# I2C_Module_v8_wo_PS.net
KiCad netlist of a schematic drawn in EAGLE
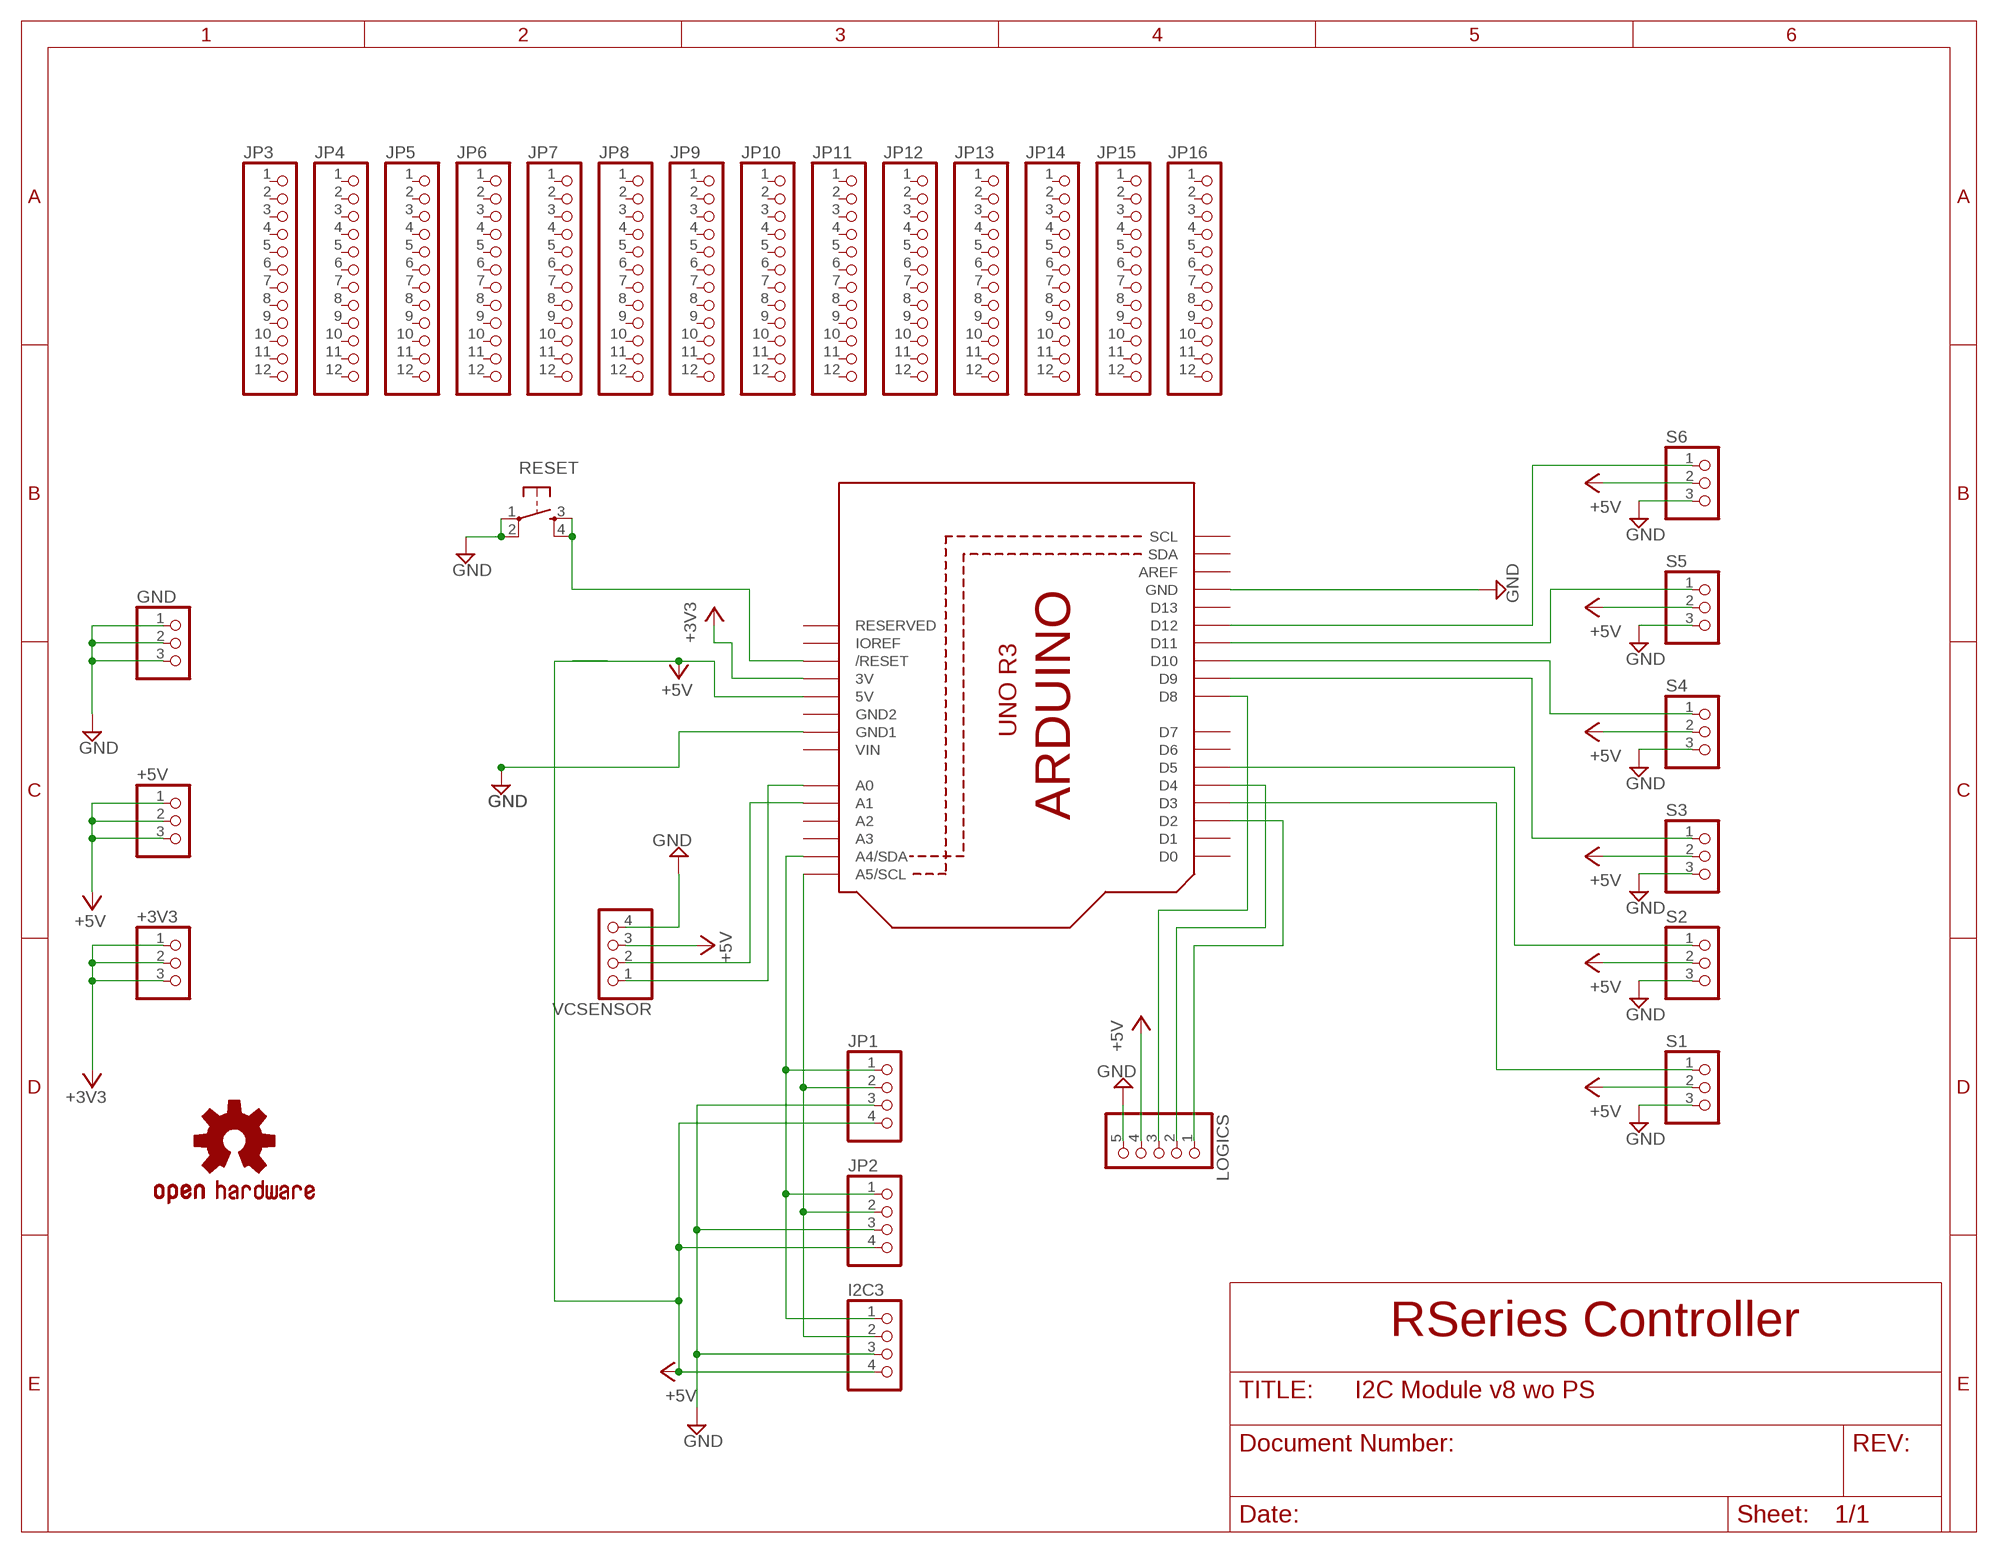
[diagram p0: schematic, sheet 1]

(export (version "E")
  (design (tool "Eeschema 10.0.6"))
  (components
    (comp (ref "+3V3")
      (value "PINHD-1X3CB")
      (footprint "eagle-import:1X03-CLEANBIG")
      (libsource (lib "eagle-import") (part "PINHD-1X3CB"))
    )
    (comp (ref "+5V")
      (value "PINHD-1X3CB")
      (footprint "eagle-import:1X03-CLEANBIG")
      (libsource (lib "eagle-import") (part "PINHD-1X3CB"))
    )
    (comp (ref "GND")
      (value "PINHD-1X3CB")
      (footprint "eagle-import:1X03-CLEANBIG")
      (libsource (lib "eagle-import") (part "PINHD-1X3CB"))
    )
    (comp (ref "I2C3")
      (value "PINHD-1X4")
      (footprint "eagle-import:1X04")
      (libsource (lib "eagle-import") (part "PINHD-1X4"))
    )
    (comp (ref "JP1")
      (value "PINHD-1X4")
      (footprint "eagle-import:1X04")
      (libsource (lib "eagle-import") (part "PINHD-1X4"))
    )
    (comp (ref "JP2")
      (value "PINHD-1X4")
      (footprint "eagle-import:1X04")
      (libsource (lib "eagle-import") (part "PINHD-1X4"))
    )
    (comp (ref "JP3")
      (value "PINHD-1X12-CB")
      (footprint "eagle-import:1X12-CB")
      (libsource (lib "eagle-import") (part "PINHD-1X12-CB"))
    )
    (comp (ref "JP4")
      (value "PINHD-1X12-CB")
      (footprint "eagle-import:1X12-CB")
      (libsource (lib "eagle-import") (part "PINHD-1X12-CB"))
    )
    (comp (ref "JP5")
      (value "PINHD-1X12-CB")
      (footprint "eagle-import:1X12-CB")
      (libsource (lib "eagle-import") (part "PINHD-1X12-CB"))
    )
    (comp (ref "JP6")
      (value "PINHD-1X12-CB")
      (footprint "eagle-import:1X12-CB")
      (libsource (lib "eagle-import") (part "PINHD-1X12-CB"))
    )
    (comp (ref "JP7")
      (value "PINHD-1X12-CB")
      (footprint "eagle-import:1X12-CB")
      (libsource (lib "eagle-import") (part "PINHD-1X12-CB"))
    )
    (comp (ref "JP8")
      (value "PINHD-1X12-CB")
      (footprint "eagle-import:1X12-CB")
      (libsource (lib "eagle-import") (part "PINHD-1X12-CB"))
    )
    (comp (ref "JP9")
      (value "PINHD-1X12-CB")
      (footprint "eagle-import:1X12-CB")
      (libsource (lib "eagle-import") (part "PINHD-1X12-CB"))
    )
    (comp (ref "JP10")
      (value "PINHD-1X12-CB")
      (footprint "eagle-import:1X12-CB")
      (libsource (lib "eagle-import") (part "PINHD-1X12-CB"))
    )
    (comp (ref "JP11")
      (value "PINHD-1X12-CB")
      (footprint "eagle-import:1X12-CB")
      (libsource (lib "eagle-import") (part "PINHD-1X12-CB"))
    )
    (comp (ref "JP12")
      (value "PINHD-1X12-CB")
      (footprint "eagle-import:1X12-CB")
      (libsource (lib "eagle-import") (part "PINHD-1X12-CB"))
    )
    (comp (ref "JP13")
      (value "PINHD-1X12-CB")
      (footprint "eagle-import:1X12-CB")
      (libsource (lib "eagle-import") (part "PINHD-1X12-CB"))
    )
    (comp (ref "JP14")
      (value "PINHD-1X12-CB")
      (footprint "eagle-import:1X12-CB")
      (libsource (lib "eagle-import") (part "PINHD-1X12-CB"))
    )
    (comp (ref "JP15")
      (value "PINHD-1X12-CB")
      (footprint "eagle-import:1X12-CB")
      (libsource (lib "eagle-import") (part "PINHD-1X12-CB"))
    )
    (comp (ref "JP16")
      (value "PINHD-1X12-CB")
      (footprint "eagle-import:1X12-CB")
      (libsource (lib "eagle-import") (part "PINHD-1X12-CB"))
    )
    (comp (ref "LOGICS")
      (value "PINHD-1X5")
      (footprint "eagle-import:1X05")
      (libsource (lib "eagle-import") (part "PINHD-1X5"))
    )
    (comp (ref "RESET")
      (value "TAC_SWITCHPTH")
      (footprint "eagle-import:TACTILE-PTH")
      (libsource (lib "eagle-import") (part "TAC_SWITCHPTH"))
    )
    (comp (ref "S1")
      (value "PINHD-1X3")
      (footprint "eagle-import:1X03")
      (libsource (lib "eagle-import") (part "PINHD-1X3"))
    )
    (comp (ref "S2")
      (value "PINHD-1X3")
      (footprint "eagle-import:1X03")
      (libsource (lib "eagle-import") (part "PINHD-1X3"))
    )
    (comp (ref "S3")
      (value "PINHD-1X3")
      (footprint "eagle-import:1X03")
      (libsource (lib "eagle-import") (part "PINHD-1X3"))
    )
    (comp (ref "S4")
      (value "PINHD-1X3")
      (footprint "eagle-import:1X03")
      (libsource (lib "eagle-import") (part "PINHD-1X3"))
    )
    (comp (ref "S5")
      (value "PINHD-1X3")
      (footprint "eagle-import:1X03")
      (libsource (lib "eagle-import") (part "PINHD-1X3"))
    )
    (comp (ref "S6")
      (value "PINHD-1X3")
      (footprint "eagle-import:1X03")
      (libsource (lib "eagle-import") (part "PINHD-1X3"))
    )
    (comp (ref "U$1")
      (value "OSHW-LOGOM")
      (footprint "eagle-import:OSHW-LOGO-M")
      (libsource (lib "eagle-import") (part "OSHW-LOGOM"))
    )
    (comp (ref "U1")
      (value "ARDUINOR3-DIMENSION")
      (footprint "eagle-import:ARDUINOR3")
      (libsource (lib "eagle-import") (part "ARDUINOR3-DIMENSION"))
    )
    (comp (ref "VCSENSOR")
      (value "PINHD-1X4")
      (footprint "eagle-import:1X04")
      (libsource (lib "eagle-import") (part "PINHD-1X4"))
    )
  )
  (nets
    (net (code "1") (name "+3V3") (class "Default")
      (node (ref "+3V3") (pin "1") (pinfunction "1_1") (pintype "passive"))
      (node (ref "+3V3") (pin "2") (pinfunction "2_2") (pintype "passive"))
      (node (ref "+3V3") (pin "3") (pinfunction "3_3") (pintype "passive"))
      (node (ref "U1") (pin "3V") (pinfunction "3V_3V") (pintype "power_in"))
    )
    (net (code "2") (name "+5V") (class "Default")
      (node (ref "+5V") (pin "1") (pinfunction "1_1") (pintype "passive"))
      (node (ref "+5V") (pin "2") (pinfunction "2_2") (pintype "passive"))
      (node (ref "+5V") (pin "3") (pinfunction "3_3") (pintype "passive"))
      (node (ref "I2C3") (pin "4") (pinfunction "4_4") (pintype "passive"))
      (node (ref "JP1") (pin "4") (pinfunction "4_4") (pintype "passive"))
      (node (ref "JP2") (pin "4") (pinfunction "4_4") (pintype "passive"))
      (node (ref "LOGICS") (pin "4") (pinfunction "4_4") (pintype "passive"))
      (node (ref "S1") (pin "2") (pinfunction "2_2") (pintype "passive"))
      (node (ref "S2") (pin "2") (pinfunction "2_2") (pintype "passive"))
      (node (ref "S3") (pin "2") (pinfunction "2_2") (pintype "passive"))
      (node (ref "S4") (pin "2") (pinfunction "2_2") (pintype "passive"))
      (node (ref "S5") (pin "2") (pinfunction "2_2") (pintype "passive"))
      (node (ref "S6") (pin "2") (pinfunction "2_2") (pintype "passive"))
      (node (ref "U1") (pin "5V") (pinfunction "5V_5V") (pintype "power_in"))
      (node (ref "VCSENSOR") (pin "3") (pinfunction "3_3") (pintype "passive"))
    )
    (net (code "3") (name "/GND2") (class "Default")
      (node (ref "U1") (pin "GND2") (pinfunction "GND2_GND2") (pintype "power_in"))
    )
    (net (code "4") (name "/VIN") (class "Default")
      (node (ref "U1") (pin "VIN") (pinfunction "VIN_VIN") (pintype "power_in"))
    )
    (net (code "5") (name "GND") (class "Default")
      (node (ref "GND") (pin "1") (pinfunction "1_1") (pintype "passive"))
      (node (ref "GND") (pin "2") (pinfunction "2_2") (pintype "passive"))
      (node (ref "GND") (pin "3") (pinfunction "3_3") (pintype "passive"))
      (node (ref "I2C3") (pin "3") (pinfunction "3_3") (pintype "passive"))
      (node (ref "JP1") (pin "3") (pinfunction "3_3") (pintype "passive"))
      (node (ref "JP2") (pin "3") (pinfunction "3_3") (pintype "passive"))
      (node (ref "LOGICS") (pin "5") (pinfunction "5_5") (pintype "passive"))
      (node (ref "RESET") (pin "1") (pinfunction "1_1") (pintype "passive"))
      (node (ref "RESET") (pin "2") (pinfunction "2_2") (pintype "passive"))
      (node (ref "S1") (pin "3") (pinfunction "3_3") (pintype "passive"))
      (node (ref "S2") (pin "3") (pinfunction "3_3") (pintype "passive"))
      (node (ref "S3") (pin "3") (pinfunction "3_3") (pintype "passive"))
      (node (ref "S4") (pin "3") (pinfunction "3_3") (pintype "passive"))
      (node (ref "S5") (pin "3") (pinfunction "3_3") (pintype "passive"))
      (node (ref "S6") (pin "3") (pinfunction "3_3") (pintype "passive"))
      (node (ref "U1") (pin "GND") (pinfunction "GND_GND") (pintype "power_in"))
      (node (ref "U1") (pin "GND1") (pinfunction "GND1_GND1") (pintype "power_in"))
      (node (ref "VCSENSOR") (pin "4") (pinfunction "4_4") (pintype "passive"))
    )
    (net (code "6") (name "Net-(LOGICS-Pad1)") (class "Default")
      (node (ref "LOGICS") (pin "1") (pinfunction "1_1") (pintype "passive"))
      (node (ref "U1") (pin "D2") (pinfunction "D2_D2") (pintype "bidirectional"))
    )
    (net (code "7") (name "Net-(LOGICS-Pad2)") (class "Default")
      (node (ref "LOGICS") (pin "2") (pinfunction "2_2") (pintype "passive"))
      (node (ref "U1") (pin "D4") (pinfunction "D4_D4") (pintype "bidirectional"))
    )
    (net (code "8") (name "Net-(LOGICS-Pad3)") (class "Default")
      (node (ref "LOGICS") (pin "3") (pinfunction "3_3") (pintype "passive"))
      (node (ref "U1") (pin "D8") (pinfunction "D8_D8") (pintype "bidirectional"))
    )
    (net (code "9") (name "Net-(S1-Pad1)") (class "Default")
      (node (ref "S1") (pin "1") (pinfunction "1_1") (pintype "passive"))
      (node (ref "U1") (pin "D3") (pinfunction "D3_D3") (pintype "bidirectional"))
    )
    (net (code "10") (name "Net-(S2-Pad1)") (class "Default")
      (node (ref "S2") (pin "1") (pinfunction "1_1") (pintype "passive"))
      (node (ref "U1") (pin "D5") (pinfunction "D5_D5") (pintype "bidirectional"))
    )
    (net (code "11") (name "Net-(S3-Pad1)") (class "Default")
      (node (ref "S3") (pin "1") (pinfunction "1_1") (pintype "passive"))
      (node (ref "U1") (pin "D9") (pinfunction "D9_D9") (pintype "bidirectional"))
    )
    (net (code "12") (name "Net-(S4-Pad1)") (class "Default")
      (node (ref "S4") (pin "1") (pinfunction "1_1") (pintype "passive"))
      (node (ref "U1") (pin "D10") (pinfunction "D10_D10") (pintype "bidirectional"))
    )
    (net (code "13") (name "Net-(S5-Pad1)") (class "Default")
      (node (ref "S5") (pin "1") (pinfunction "1_1") (pintype "passive"))
      (node (ref "U1") (pin "D11") (pinfunction "D11_D11") (pintype "bidirectional"))
    )
    (net (code "14") (name "Net-(S6-Pad1)") (class "Default")
      (node (ref "S6") (pin "1") (pinfunction "1_1") (pintype "passive"))
      (node (ref "U1") (pin "D12") (pinfunction "D12_D12") (pintype "bidirectional"))
    )
    (net (code "15") (name "Net-(U1-A4{slash}SDA)") (class "Default")
      (node (ref "I2C3") (pin "1") (pinfunction "1_1") (pintype "passive"))
      (node (ref "JP1") (pin "1") (pinfunction "1_1") (pintype "passive"))
      (node (ref "JP2") (pin "1") (pinfunction "1_1") (pintype "passive"))
      (node (ref "U1") (pin "A4") (pinfunction "A4/SDA_A4") (pintype "bidirectional"))
    )
    (net (code "16") (name "Net-(U1-A5{slash}SCL)") (class "Default")
      (node (ref "I2C3") (pin "2") (pinfunction "2_2") (pintype "passive"))
      (node (ref "JP1") (pin "2") (pinfunction "2_2") (pintype "passive"))
      (node (ref "JP2") (pin "2") (pinfunction "2_2") (pintype "passive"))
      (node (ref "U1") (pin "A5") (pinfunction "A5/SCL_A5") (pintype "bidirectional"))
    )
    (net (code "17") (name "Net-(U1-PadA0)") (class "Default")
      (node (ref "U1") (pin "A0") (pinfunction "A0_A0") (pintype "bidirectional"))
      (node (ref "VCSENSOR") (pin "1") (pinfunction "1_1") (pintype "passive"))
    )
    (net (code "18") (name "Net-(U1-PadA1)") (class "Default")
      (node (ref "U1") (pin "A1") (pinfunction "A1_A1") (pintype "bidirectional"))
      (node (ref "VCSENSOR") (pin "2") (pinfunction "2_2") (pintype "passive"))
    )
    (net (code "19") (name "Net-(U1-{slash}RESET)") (class "Default")
      (node (ref "RESET") (pin "3") (pinfunction "3_3") (pintype "passive"))
      (node (ref "RESET") (pin "4") (pinfunction "4_4") (pintype "passive"))
      (node (ref "U1") (pin "RESET") (pinfunction "/RESET_RESET") (pintype "bidirectional"))
    )
    (net (code "20") (name "unconnected-(JP3-Pad1)") (class "Default")
      (node (ref "JP3") (pin "1") (pinfunction "1_1") (pintype "passive"))
    )
    (net (code "21") (name "unconnected-(JP3-Pad2)") (class "Default")
      (node (ref "JP3") (pin "2") (pinfunction "2_2") (pintype "passive"))
    )
    (net (code "22") (name "unconnected-(JP3-Pad3)") (class "Default")
      (node (ref "JP3") (pin "3") (pinfunction "3_3") (pintype "passive"))
    )
    (net (code "23") (name "unconnected-(JP3-Pad4)") (class "Default")
      (node (ref "JP3") (pin "4") (pinfunction "4_4") (pintype "passive"))
    )
    (net (code "24") (name "unconnected-(JP3-Pad5)") (class "Default")
      (node (ref "JP3") (pin "5") (pinfunction "5_5") (pintype "passive"))
    )
    (net (code "25") (name "unconnected-(JP3-Pad6)") (class "Default")
      (node (ref "JP3") (pin "6") (pinfunction "6_6") (pintype "passive"))
    )
    (net (code "26") (name "unconnected-(JP3-Pad7)") (class "Default")
      (node (ref "JP3") (pin "7") (pinfunction "7_7") (pintype "passive"))
    )
    (net (code "27") (name "unconnected-(JP3-Pad8)") (class "Default")
      (node (ref "JP3") (pin "8") (pinfunction "8_8") (pintype "passive"))
    )
    (net (code "28") (name "unconnected-(JP3-Pad9)") (class "Default")
      (node (ref "JP3") (pin "9") (pinfunction "9_9") (pintype "passive"))
    )
    (net (code "29") (name "unconnected-(JP3-Pad10)") (class "Default")
      (node (ref "JP3") (pin "10") (pinfunction "10_10") (pintype "passive"))
    )
    (net (code "30") (name "unconnected-(JP3-Pad11)") (class "Default")
      (node (ref "JP3") (pin "11") (pinfunction "11_11") (pintype "passive"))
    )
    (net (code "31") (name "unconnected-(JP3-Pad12)") (class "Default")
      (node (ref "JP3") (pin "12") (pinfunction "12_12") (pintype "passive"))
    )
    (net (code "32") (name "unconnected-(JP4-Pad1)") (class "Default")
      (node (ref "JP4") (pin "1") (pinfunction "1_1") (pintype "passive"))
    )
    (net (code "33") (name "unconnected-(JP4-Pad2)") (class "Default")
      (node (ref "JP4") (pin "2") (pinfunction "2_2") (pintype "passive"))
    )
    (net (code "34") (name "unconnected-(JP4-Pad3)") (class "Default")
      (node (ref "JP4") (pin "3") (pinfunction "3_3") (pintype "passive"))
    )
    (net (code "35") (name "unconnected-(JP4-Pad4)") (class "Default")
      (node (ref "JP4") (pin "4") (pinfunction "4_4") (pintype "passive"))
    )
    (net (code "36") (name "unconnected-(JP4-Pad5)") (class "Default")
      (node (ref "JP4") (pin "5") (pinfunction "5_5") (pintype "passive"))
    )
    (net (code "37") (name "unconnected-(JP4-Pad6)") (class "Default")
      (node (ref "JP4") (pin "6") (pinfunction "6_6") (pintype "passive"))
    )
    (net (code "38") (name "unconnected-(JP4-Pad7)") (class "Default")
      (node (ref "JP4") (pin "7") (pinfunction "7_7") (pintype "passive"))
    )
    (net (code "39") (name "unconnected-(JP4-Pad8)") (class "Default")
      (node (ref "JP4") (pin "8") (pinfunction "8_8") (pintype "passive"))
    )
    (net (code "40") (name "unconnected-(JP4-Pad9)") (class "Default")
      (node (ref "JP4") (pin "9") (pinfunction "9_9") (pintype "passive"))
    )
    (net (code "41") (name "unconnected-(JP4-Pad10)") (class "Default")
      (node (ref "JP4") (pin "10") (pinfunction "10_10") (pintype "passive"))
    )
    (net (code "42") (name "unconnected-(JP4-Pad11)") (class "Default")
      (node (ref "JP4") (pin "11") (pinfunction "11_11") (pintype "passive"))
    )
    (net (code "43") (name "unconnected-(JP4-Pad12)") (class "Default")
      (node (ref "JP4") (pin "12") (pinfunction "12_12") (pintype "passive"))
    )
    (net (code "44") (name "unconnected-(JP5-Pad1)") (class "Default")
      (node (ref "JP5") (pin "1") (pinfunction "1_1") (pintype "passive"))
    )
    (net (code "45") (name "unconnected-(JP5-Pad2)") (class "Default")
      (node (ref "JP5") (pin "2") (pinfunction "2_2") (pintype "passive"))
    )
    (net (code "46") (name "unconnected-(JP5-Pad3)") (class "Default")
      (node (ref "JP5") (pin "3") (pinfunction "3_3") (pintype "passive"))
    )
    (net (code "47") (name "unconnected-(JP5-Pad4)") (class "Default")
      (node (ref "JP5") (pin "4") (pinfunction "4_4") (pintype "passive"))
    )
    (net (code "48") (name "unconnected-(JP5-Pad5)") (class "Default")
      (node (ref "JP5") (pin "5") (pinfunction "5_5") (pintype "passive"))
    )
    (net (code "49") (name "unconnected-(JP5-Pad6)") (class "Default")
      (node (ref "JP5") (pin "6") (pinfunction "6_6") (pintype "passive"))
    )
    (net (code "50") (name "unconnected-(JP5-Pad7)") (class "Default")
      (node (ref "JP5") (pin "7") (pinfunction "7_7") (pintype "passive"))
    )
    (net (code "51") (name "unconnected-(JP5-Pad8)") (class "Default")
      (node (ref "JP5") (pin "8") (pinfunction "8_8") (pintype "passive"))
    )
    (net (code "52") (name "unconnected-(JP5-Pad9)") (class "Default")
      (node (ref "JP5") (pin "9") (pinfunction "9_9") (pintype "passive"))
    )
    (net (code "53") (name "unconnected-(JP5-Pad10)") (class "Default")
      (node (ref "JP5") (pin "10") (pinfunction "10_10") (pintype "passive"))
    )
    (net (code "54") (name "unconnected-(JP5-Pad11)") (class "Default")
      (node (ref "JP5") (pin "11") (pinfunction "11_11") (pintype "passive"))
    )
    (net (code "55") (name "unconnected-(JP5-Pad12)") (class "Default")
      (node (ref "JP5") (pin "12") (pinfunction "12_12") (pintype "passive"))
    )
    (net (code "56") (name "unconnected-(JP6-Pad1)") (class "Default")
      (node (ref "JP6") (pin "1") (pinfunction "1_1") (pintype "passive"))
    )
    (net (code "57") (name "unconnected-(JP6-Pad2)") (class "Default")
      (node (ref "JP6") (pin "2") (pinfunction "2_2") (pintype "passive"))
    )
    (net (code "58") (name "unconnected-(JP6-Pad3)") (class "Default")
      (node (ref "JP6") (pin "3") (pinfunction "3_3") (pintype "passive"))
    )
    (net (code "59") (name "unconnected-(JP6-Pad4)") (class "Default")
      (node (ref "JP6") (pin "4") (pinfunction "4_4") (pintype "passive"))
    )
    (net (code "60") (name "unconnected-(JP6-Pad5)") (class "Default")
      (node (ref "JP6") (pin "5") (pinfunction "5_5") (pintype "passive"))
    )
    (net (code "61") (name "unconnected-(JP6-Pad6)") (class "Default")
      (node (ref "JP6") (pin "6") (pinfunction "6_6") (pintype "passive"))
    )
    (net (code "62") (name "unconnected-(JP6-Pad7)") (class "Default")
      (node (ref "JP6") (pin "7") (pinfunction "7_7") (pintype "passive"))
    )
    (net (code "63") (name "unconnected-(JP6-Pad8)") (class "Default")
      (node (ref "JP6") (pin "8") (pinfunction "8_8") (pintype "passive"))
    )
    (net (code "64") (name "unconnected-(JP6-Pad9)") (class "Default")
      (node (ref "JP6") (pin "9") (pinfunction "9_9") (pintype "passive"))
    )
    (net (code "65") (name "unconnected-(JP6-Pad10)") (class "Default")
      (node (ref "JP6") (pin "10") (pinfunction "10_10") (pintype "passive"))
    )
    (net (code "66") (name "unconnected-(JP6-Pad11)") (class "Default")
      (node (ref "JP6") (pin "11") (pinfunction "11_11") (pintype "passive"))
    )
    (net (code "67") (name "unconnected-(JP6-Pad12)") (class "Default")
      (node (ref "JP6") (pin "12") (pinfunction "12_12") (pintype "passive"))
    )
    (net (code "68") (name "unconnected-(JP7-Pad1)") (class "Default")
      (node (ref "JP7") (pin "1") (pinfunction "1_1") (pintype "passive"))
    )
    (net (code "69") (name "unconnected-(JP7-Pad2)") (class "Default")
      (node (ref "JP7") (pin "2") (pinfunction "2_2") (pintype "passive"))
    )
    (net (code "70") (name "unconnected-(JP7-Pad3)") (class "Default")
      (node (ref "JP7") (pin "3") (pinfunction "3_3") (pintype "passive"))
    )
    (net (code "71") (name "unconnected-(JP7-Pad4)") (class "Default")
      (node (ref "JP7") (pin "4") (pinfunction "4_4") (pintype "passive"))
    )
    (net (code "72") (name "unconnected-(JP7-Pad5)") (class "Default")
      (node (ref "JP7") (pin "5") (pinfunction "5_5") (pintype "passive"))
    )
    (net (code "73") (name "unconnected-(JP7-Pad6)") (class "Default")
      (node (ref "JP7") (pin "6") (pinfunction "6_6") (pintype "passive"))
    )
    (net (code "74") (name "unconnected-(JP7-Pad7)") (class "Default")
      (node (ref "JP7") (pin "7") (pinfunction "7_7") (pintype "passive"))
    )
    (net (code "75") (name "unconnected-(JP7-Pad8)") (class "Default")
      (node (ref "JP7") (pin "8") (pinfunction "8_8") (pintype "passive"))
    )
    (net (code "76") (name "unconnected-(JP7-Pad9)") (class "Default")
      (node (ref "JP7") (pin "9") (pinfunction "9_9") (pintype "passive"))
    )
    (net (code "77") (name "unconnected-(JP7-Pad10)") (class "Default")
      (node (ref "JP7") (pin "10") (pinfunction "10_10") (pintype "passive"))
    )
    (net (code "78") (name "unconnected-(JP7-Pad11)") (class "Default")
      (node (ref "JP7") (pin "11") (pinfunction "11_11") (pintype "passive"))
    )
    (net (code "79") (name "unconnected-(JP7-Pad12)") (class "Default")
      (node (ref "JP7") (pin "12") (pinfunction "12_12") (pintype "passive"))
    )
    (net (code "80") (name "unconnected-(JP8-Pad1)") (class "Default")
      (node (ref "JP8") (pin "1") (pinfunction "1_1") (pintype "passive"))
    )
    (net (code "81") (name "unconnected-(JP8-Pad2)") (class "Default")
      (node (ref "JP8") (pin "2") (pinfunction "2_2") (pintype "passive"))
    )
    (net (code "82") (name "unconnected-(JP8-Pad3)") (class "Default")
      (node (ref "JP8") (pin "3") (pinfunction "3_3") (pintype "passive"))
    )
    (net (code "83") (name "unconnected-(JP8-Pad4)") (class "Default")
      (node (ref "JP8") (pin "4") (pinfunction "4_4") (pintype "passive"))
    )
    (net (code "84") (name "unconnected-(JP8-Pad5)") (class "Default")
      (node (ref "JP8") (pin "5") (pinfunction "5_5") (pintype "passive"))
    )
    (net (code "85") (name "unconnected-(JP8-Pad6)") (class "Default")
      (node (ref "JP8") (pin "6") (pinfunction "6_6") (pintype "passive"))
    )
    (net (code "86") (name "unconnected-(JP8-Pad7)") (class "Default")
      (node (ref "JP8") (pin "7") (pinfunction "7_7") (pintype "passive"))
    )
    (net (code "87") (name "unconnected-(JP8-Pad8)") (class "Default")
      (node (ref "JP8") (pin "8") (pinfunction "8_8") (pintype "passive"))
    )
    (net (code "88") (name "unconnected-(JP8-Pad9)") (class "Default")
      (node (ref "JP8") (pin "9") (pinfunction "9_9") (pintype "passive"))
    )
    (net (code "89") (name "unconnected-(JP8-Pad10)") (class "Default")
      (node (ref "JP8") (pin "10") (pinfunction "10_10") (pintype "passive"))
    )
    (net (code "90") (name "unconnected-(JP8-Pad11)") (class "Default")
      (node (ref "JP8") (pin "11") (pinfunction "11_11") (pintype "passive"))
    )
    (net (code "91") (name "unconnected-(JP8-Pad12)") (class "Default")
      (node (ref "JP8") (pin "12") (pinfunction "12_12") (pintype "passive"))
    )
    (net (code "92") (name "unconnected-(JP9-Pad1)") (class "Default")
      (node (ref "JP9") (pin "1") (pinfunction "1_1") (pintype "passive"))
    )
    (net (code "93") (name "unconnected-(JP9-Pad2)") (class "Default")
      (node (ref "JP9") (pin "2") (pinfunction "2_2") (pintype "passive"))
    )
    (net (code "94") (name "unconnected-(JP9-Pad3)") (class "Default")
      (node (ref "JP9") (pin "3") (pinfunction "3_3") (pintype "passive"))
    )
    (net (code "95") (name "unconnected-(JP9-Pad4)") (class "Default")
      (node (ref "JP9") (pin "4") (pinfunction "4_4") (pintype "passive"))
    )
    (net (code "96") (name "unconnected-(JP9-Pad5)") (class "Default")
      (node (ref "JP9") (pin "5") (pinfunction "5_5") (pintype "passive"))
    )
    (net (code "97") (name "unconnected-(JP9-Pad6)") (class "Default")
      (node (ref "JP9") (pin "6") (pinfunction "6_6") (pintype "passive"))
    )
    (net (code "98") (name "unconnected-(JP9-Pad7)") (class "Default")
      (node (ref "JP9") (pin "7") (pinfunction "7_7") (pintype "passive"))
    )
    (net (code "99") (name "unconnected-(JP9-Pad8)") (class "Default")
      (node (ref "JP9") (pin "8") (pinfunction "8_8") (pintype "passive"))
    )
    (net (code "100") (name "unconnected-(JP9-Pad9)") (class "Default")
      (node (ref "JP9") (pin "9") (pinfunction "9_9") (pintype "passive"))
    )
    (net (code "101") (name "unconnected-(JP9-Pad10)") (class "Default")
      (node (ref "JP9") (pin "10") (pinfunction "10_10") (pintype "passive"))
    )
    (net (code "102") (name "unconnected-(JP9-Pad11)") (class "Default")
      (node (ref "JP9") (pin "11") (pinfunction "11_11") (pintype "passive"))
    )
    (net (code "103") (name "unconnected-(JP9-Pad12)") (class "Default")
      (node (ref "JP9") (pin "12") (pinfunction "12_12") (pintype "passive"))
    )
    (net (code "104") (name "unconnected-(JP10-Pad1)") (class "Default")
      (node (ref "JP10") (pin "1") (pinfunction "1_1") (pintype "passive"))
    )
    (net (code "105") (name "unconnected-(JP10-Pad2)") (class "Default")
      (node (ref "JP10") (pin "2") (pinfunction "2_2") (pintype "passive"))
    )
    (net (code "106") (name "unconnected-(JP10-Pad3)") (class "Default")
      (node (ref "JP10") (pin "3") (pinfunction "3_3") (pintype "passive"))
    )
    (net (code "107") (name "unconnected-(JP10-Pad4)") (class "Default")
      (node (ref "JP10") (pin "4") (pinfunction "4_4") (pintype "passive"))
    )
    (net (code "108") (name "unconnected-(JP10-Pad5)") (class "Default")
      (node (ref "JP10") (pin "5") (pinfunction "5_5") (pintype "passive"))
    )
    (net (code "109") (name "unconnected-(JP10-Pad6)") (class "Default")
      (node (ref "JP10") (pin "6") (pinfunction "6_6") (pintype "passive"))
    )
    (net (code "110") (name "unconnected-(JP10-Pad7)") (class "Default")
      (node (ref "JP10") (pin "7") (pinfunction "7_7") (pintype "passive"))
    )
    (net (code "111") (name "unconnected-(JP10-Pad8)") (class "Default")
      (node (ref "JP10") (pin "8") (pinfunction "8_8") (pintype "passive"))
    )
    (net (code "112") (name "unconnected-(JP10-Pad9)") (class "Default")
      (node (ref "JP10") (pin "9") (pinfunction "9_9") (pintype "passive"))
    )
    (net (code "113") (name "unconnected-(JP10-Pad10)") (class "Default")
      (node (ref "JP10") (pin "10") (pinfunction "10_10") (pintype "passive"))
    )
    (net (code "114") (name "unconnected-(JP10-Pad11)") (class "Default")
      (node (ref "JP10") (pin "11") (pinfunction "11_11") (pintype "passive"))
    )
    (net (code "115") (name "unconnected-(JP10-Pad12)") (class "Default")
      (node (ref "JP10") (pin "12") (pinfunction "12_12") (pintype "passive"))
    )
    (net (code "116") (name "unconnected-(JP11-Pad1)") (class "Default")
      (node (ref "JP11") (pin "1") (pinfunction "1_1") (pintype "passive"))
    )
    (net (code "117") (name "unconnected-(JP11-Pad2)") (class "Default")
      (node (ref "JP11") (pin "2") (pinfunction "2_2") (pintype "passive"))
    )
    (net (code "118") (name "unconnected-(JP11-Pad3)") (class "Default")
      (node (ref "JP11") (pin "3") (pinfunction "3_3") (pintype "passive"))
    )
    (net (code "119") (name "unconnected-(JP11-Pad4)") (class "Default")
      (node (ref "JP11") (pin "4") (pinfunction "4_4") (pintype "passive"))
    )
    (net (code "120") (name "unconnected-(JP11-Pad5)") (class "Default")
      (node (ref "JP11") (pin "5") (pinfunction "5_5") (pintype "passive"))
    )
    (net (code "121") (name "unconnected-(JP11-Pad6)") (class "Default")
      (node (ref "JP11") (pin "6") (pinfunction "6_6") (pintype "passive"))
    )
    (net (code "122") (name "unconnected-(JP11-Pad7)") (class "Default")
      (node (ref "JP11") (pin "7") (pinfunction "7_7") (pintype "passive"))
    )
    (net (code "123") (name "unconnected-(JP11-Pad8)") (class "Default")
      (node (ref "JP11") (pin "8") (pinfunction "8_8") (pintype "passive"))
    )
    (net (code "124") (name "unconnected-(JP11-Pad9)") (class "Default")
      (node (ref "JP11") (pin "9") (pinfunction "9_9") (pintype "passive"))
    )
    (net (code "125") (name "unconnected-(JP11-Pad10)") (class "Default")
      (node (ref "JP11") (pin "10") (pinfunction "10_10") (pintype "passive"))
    )
    (net (code "126") (name "unconnected-(JP11-Pad11)") (class "Default")
      (node (ref "JP11") (pin "11") (pinfunction "11_11") (pintype "passive"))
    )
    (net (code "127") (name "unconnected-(JP11-Pad12)") (class "Default")
      (node (ref "JP11") (pin "12") (pinfunction "12_12") (pintype "passive"))
    )
    (net (code "128") (name "unconnected-(JP12-Pad1)") (class "Default")
      (node (ref "JP12") (pin "1") (pinfunction "1_1") (pintype "passive"))
    )
    (net (code "129") (name "unconnected-(JP12-Pad2)") (class "Default")
      (node (ref "JP12") (pin "2") (pinfunction "2_2") (pintype "passive"))
    )
    (net (code "130") (name "unconnected-(JP12-Pad3)") (class "Default")
      (node (ref "JP12") (pin "3") (pinfunction "3_3") (pintype "passive"))
    )
    (net (code "131") (name "unconnected-(JP12-Pad4)") (class "Default")
      (node (ref "JP12") (pin "4") (pinfunction "4_4") (pintype "passive"))
    )
    (net (code "132") (name "unconnected-(JP12-Pad5)") (class "Default")
      (node (ref "JP12") (pin "5") (pinfunction "5_5") (pintype "passive"))
    )
    (net (code "133") (name "unconnected-(JP12-Pad6)") (class "Default")
      (node (ref "JP12") (pin "6") (pinfunction "6_6") (pintype "passive"))
    )
    (net (code "134") (name "unconnected-(JP12-Pad7)") (class "Default")
      (node (ref "JP12") (pin "7") (pinfunction "7_7") (pintype "passive"))
    )
    (net (code "135") (name "unconnected-(JP12-Pad8)") (class "Default")
      (node (ref "JP12") (pin "8") (pinfunction "8_8") (pintype "passive"))
    )
    (net (code "136") (name "unconnected-(JP12-Pad9)") (class "Default")
      (node (ref "JP12") (pin "9") (pinfunction "9_9") (pintype "passive"))
    )
    (net (code "137") (name "unconnected-(JP12-Pad10)") (class "Default")
      (node (ref "JP12") (pin "10") (pinfunction "10_10") (pintype "passive"))
    )
    (net (code "138") (name "unconnected-(JP12-Pad11)") (class "Default")
      (node (ref "JP12") (pin "11") (pinfunction "11_11") (pintype "passive"))
    )
    (net (code "139") (name "unconnected-(JP12-Pad12)") (class "Default")
      (node (ref "JP12") (pin "12") (pinfunction "12_12") (pintype "passive"))
    )
    (net (code "140") (name "unconnected-(JP13-Pad1)") (class "Default")
      (node (ref "JP13") (pin "1") (pinfunction "1_1") (pintype "passive"))
    )
    (net (code "141") (name "unconnected-(JP13-Pad2)") (class "Default")
      (node (ref "JP13") (pin "2") (pinfunction "2_2") (pintype "passive"))
    )
    (net (code "142") (name "unconnected-(JP13-Pad3)") (class "Default")
      (node (ref "JP13") (pin "3") (pinfunction "3_3") (pintype "passive"))
    )
    (net (code "143") (name "unconnected-(JP13-Pad4)") (class "Default")
      (node (ref "JP13") (pin "4") (pinfunction "4_4") (pintype "passive"))
    )
    (net (code "144") (name "unconnected-(JP13-Pad5)") (class "Default")
      (node (ref "JP13") (pin "5") (pinfunction "5_5") (pintype "passive"))
    )
    (net (code "145") (name "unconnected-(JP13-Pad6)") (class "Default")
      (node (ref "JP13") (pin "6") (pinfunction "6_6") (pintype "passive"))
    )
    (net (code "146") (name "unconnected-(JP13-Pad7)") (class "Default")
      (node (ref "JP13") (pin "7") (pinfunction "7_7") (pintype "passive"))
    )
    (net (code "147") (name "unconnected-(JP13-Pad8)") (class "Default")
      (node (ref "JP13") (pin "8") (pinfunction "8_8") (pintype "passive"))
    )
    (net (code "148") (name "unconnected-(JP13-Pad9)") (class "Default")
      (node (ref "JP13") (pin "9") (pinfunction "9_9") (pintype "passive"))
    )
    (net (code "149") (name "unconnected-(JP13-Pad10)") (class "Default")
      (node (ref "JP13") (pin "10") (pinfunction "10_10") (pintype "passive"))
    )
    (net (code "150") (name "unconnected-(JP13-Pad11)") (class "Default")
      (node (ref "JP13") (pin "11") (pinfunction "11_11") (pintype "passive"))
    )
    (net (code "151") (name "unconnected-(JP13-Pad12)") (class "Default")
      (node (ref "JP13") (pin "12") (pinfunction "12_12") (pintype "passive"))
    )
    (net (code "152") (name "unconnected-(JP14-Pad1)") (class "Default")
      (node (ref "JP14") (pin "1") (pinfunction "1_1") (pintype "passive"))
    )
    (net (code "153") (name "unconnected-(JP14-Pad2)") (class "Default")
      (node (ref "JP14") (pin "2") (pinfunction "2_2") (pintype "passive"))
    )
    (net (code "154") (name "unconnected-(JP14-Pad3)") (class "Default")
      (node (ref "JP14") (pin "3") (pinfunction "3_3") (pintype "passive"))
    )
    (net (code "155") (name "unconnected-(JP14-Pad4)") (class "Default")
      (node (ref "JP14") (pin "4") (pinfunction "4_4") (pintype "passive"))
    )
    (net (code "156") (name "unconnected-(JP14-Pad5)") (class "Default")
      (node (ref "JP14") (pin "5") (pinfunction "5_5") (pintype "passive"))
    )
    (net (code "157") (name "unconnected-(JP14-Pad6)") (class "Default")
      (node (ref "JP14") (pin "6") (pinfunction "6_6") (pintype "passive"))
    )
    (net (code "158") (name "unconnected-(JP14-Pad7)") (class "Default")
      (node (ref "JP14") (pin "7") (pinfunction "7_7") (pintype "passive"))
    )
    (net (code "159") (name "unconnected-(JP14-Pad8)") (class "Default")
      (node (ref "JP14") (pin "8") (pinfunction "8_8") (pintype "passive"))
    )
    (net (code "160") (name "unconnected-(JP14-Pad9)") (class "Default")
      (node (ref "JP14") (pin "9") (pinfunction "9_9") (pintype "passive"))
    )
    (net (code "161") (name "unconnected-(JP14-Pad10)") (class "Default")
      (node (ref "JP14") (pin "10") (pinfunction "10_10") (pintype "passive"))
    )
    (net (code "162") (name "unconnected-(JP14-Pad11)") (class "Default")
      (node (ref "JP14") (pin "11") (pinfunction "11_11") (pintype "passive"))
    )
    (net (code "163") (name "unconnected-(JP14-Pad12)") (class "Default")
      (node (ref "JP14") (pin "12") (pinfunction "12_12") (pintype "passive"))
    )
    (net (code "164") (name "unconnected-(JP15-Pad1)") (class "Default")
      (node (ref "JP15") (pin "1") (pinfunction "1_1") (pintype "passive"))
    )
    (net (code "165") (name "unconnected-(JP15-Pad2)") (class "Default")
      (node (ref "JP15") (pin "2") (pinfunction "2_2") (pintype "passive"))
    )
    (net (code "166") (name "unconnected-(JP15-Pad3)") (class "Default")
      (node (ref "JP15") (pin "3") (pinfunction "3_3") (pintype "passive"))
    )
    (net (code "167") (name "unconnected-(JP15-Pad4)") (class "Default")
      (node (ref "JP15") (pin "4") (pinfunction "4_4") (pintype "passive"))
    )
    (net (code "168") (name "unconnected-(JP15-Pad5)") (class "Default")
      (node (ref "JP15") (pin "5") (pinfunction "5_5") (pintype "passive"))
    )
    (net (code "169") (name "unconnected-(JP15-Pad6)") (class "Default")
      (node (ref "JP15") (pin "6") (pinfunction "6_6") (pintype "passive"))
    )
    (net (code "170") (name "unconnected-(JP15-Pad7)") (class "Default")
      (node (ref "JP15") (pin "7") (pinfunction "7_7") (pintype "passive"))
    )
    (net (code "171") (name "unconnected-(JP15-Pad8)") (class "Default")
      (node (ref "JP15") (pin "8") (pinfunction "8_8") (pintype "passive"))
    )
    (net (code "172") (name "unconnected-(JP15-Pad9)") (class "Default")
      (node (ref "JP15") (pin "9") (pinfunction "9_9") (pintype "passive"))
    )
    (net (code "173") (name "unconnected-(JP15-Pad10)") (class "Default")
      (node (ref "JP15") (pin "10") (pinfunction "10_10") (pintype "passive"))
    )
    (net (code "174") (name "unconnected-(JP15-Pad11)") (class "Default")
      (node (ref "JP15") (pin "11") (pinfunction "11_11") (pintype "passive"))
    )
    (net (code "175") (name "unconnected-(JP15-Pad12)") (class "Default")
      (node (ref "JP15") (pin "12") (pinfunction "12_12") (pintype "passive"))
    )
    (net (code "176") (name "unconnected-(JP16-Pad1)") (class "Default")
      (node (ref "JP16") (pin "1") (pinfunction "1_1") (pintype "passive"))
    )
    (net (code "177") (name "unconnected-(JP16-Pad2)") (class "Default")
      (node (ref "JP16") (pin "2") (pinfunction "2_2") (pintype "passive"))
    )
    (net (code "178") (name "unconnected-(JP16-Pad3)") (class "Default")
      (node (ref "JP16") (pin "3") (pinfunction "3_3") (pintype "passive"))
    )
    (net (code "179") (name "unconnected-(JP16-Pad4)") (class "Default")
      (node (ref "JP16") (pin "4") (pinfunction "4_4") (pintype "passive"))
    )
    (net (code "180") (name "unconnected-(JP16-Pad5)") (class "Default")
      (node (ref "JP16") (pin "5") (pinfunction "5_5") (pintype "passive"))
    )
    (net (code "181") (name "unconnected-(JP16-Pad6)") (class "Default")
      (node (ref "JP16") (pin "6") (pinfunction "6_6") (pintype "passive"))
    )
    (net (code "182") (name "unconnected-(JP16-Pad7)") (class "Default")
      (node (ref "JP16") (pin "7") (pinfunction "7_7") (pintype "passive"))
    )
    (net (code "183") (name "unconnected-(JP16-Pad8)") (class "Default")
      (node (ref "JP16") (pin "8") (pinfunction "8_8") (pintype "passive"))
    )
    (net (code "184") (name "unconnected-(JP16-Pad9)") (class "Default")
      (node (ref "JP16") (pin "9") (pinfunction "9_9") (pintype "passive"))
    )
    (net (code "185") (name "unconnected-(JP16-Pad10)") (class "Default")
      (node (ref "JP16") (pin "10") (pinfunction "10_10") (pintype "passive"))
    )
    (net (code "186") (name "unconnected-(JP16-Pad11)") (class "Default")
      (node (ref "JP16") (pin "11") (pinfunction "11_11") (pintype "passive"))
    )
    (net (code "187") (name "unconnected-(JP16-Pad12)") (class "Default")
      (node (ref "JP16") (pin "12") (pinfunction "12_12") (pintype "passive"))
    )
    (net (code "188") (name "unconnected-(U1-PadA2)") (class "Default")
      (node (ref "U1") (pin "A2") (pinfunction "A2_A2") (pintype "bidirectional"))
    )
    (net (code "189") (name "unconnected-(U1-PadA3)") (class "Default")
      (node (ref "U1") (pin "A3") (pinfunction "A3_A3") (pintype "bidirectional"))
    )
    (net (code "190") (name "unconnected-(U1-PadAREF)") (class "Default")
      (node (ref "U1") (pin "AREF") (pinfunction "AREF_AREF") (pintype "bidirectional"))
    )
    (net (code "191") (name "unconnected-(U1-PadD0)") (class "Default")
      (node (ref "U1") (pin "D0") (pinfunction "D0_D0") (pintype "bidirectional"))
    )
    (net (code "192") (name "unconnected-(U1-PadD1)") (class "Default")
      (node (ref "U1") (pin "D1") (pinfunction "D1_D1") (pintype "bidirectional"))
    )
    (net (code "193") (name "unconnected-(U1-PadD6)") (class "Default")
      (node (ref "U1") (pin "D6") (pinfunction "D6_D6") (pintype "bidirectional"))
    )
    (net (code "194") (name "unconnected-(U1-PadD7)") (class "Default")
      (node (ref "U1") (pin "D7") (pinfunction "D7_D7") (pintype "bidirectional"))
    )
    (net (code "195") (name "unconnected-(U1-PadD13)") (class "Default")
      (node (ref "U1") (pin "D13") (pinfunction "D13_D13") (pintype "bidirectional"))
    )
    (net (code "196") (name "unconnected-(U1-PadIOREF)") (class "Default")
      (node (ref "U1") (pin "IOREF") (pinfunction "IOREF_IOREF") (pintype "output"))
    )
    (net (code "197") (name "unconnected-(U1-PadRESERVED)") (class "Default")
      (node (ref "U1") (pin "RESERVED") (pinfunction "RESERVED_RESERVED") (pintype "no_connect"))
    )
    (net (code "198") (name "unconnected-(U1-PadSCL)") (class "Default")
      (node (ref "U1") (pin "SCL") (pinfunction "SCL_SCL") (pintype "bidirectional"))
    )
    (net (code "199") (name "unconnected-(U1-PadSDA)") (class "Default")
      (node (ref "U1") (pin "SDA") (pinfunction "SDA_SDA") (pintype "bidirectional"))
    )
  )
)
